# 2LD-20-mk-1_1_1.net
KiCad netlist of a schematic drawn in EAGLE
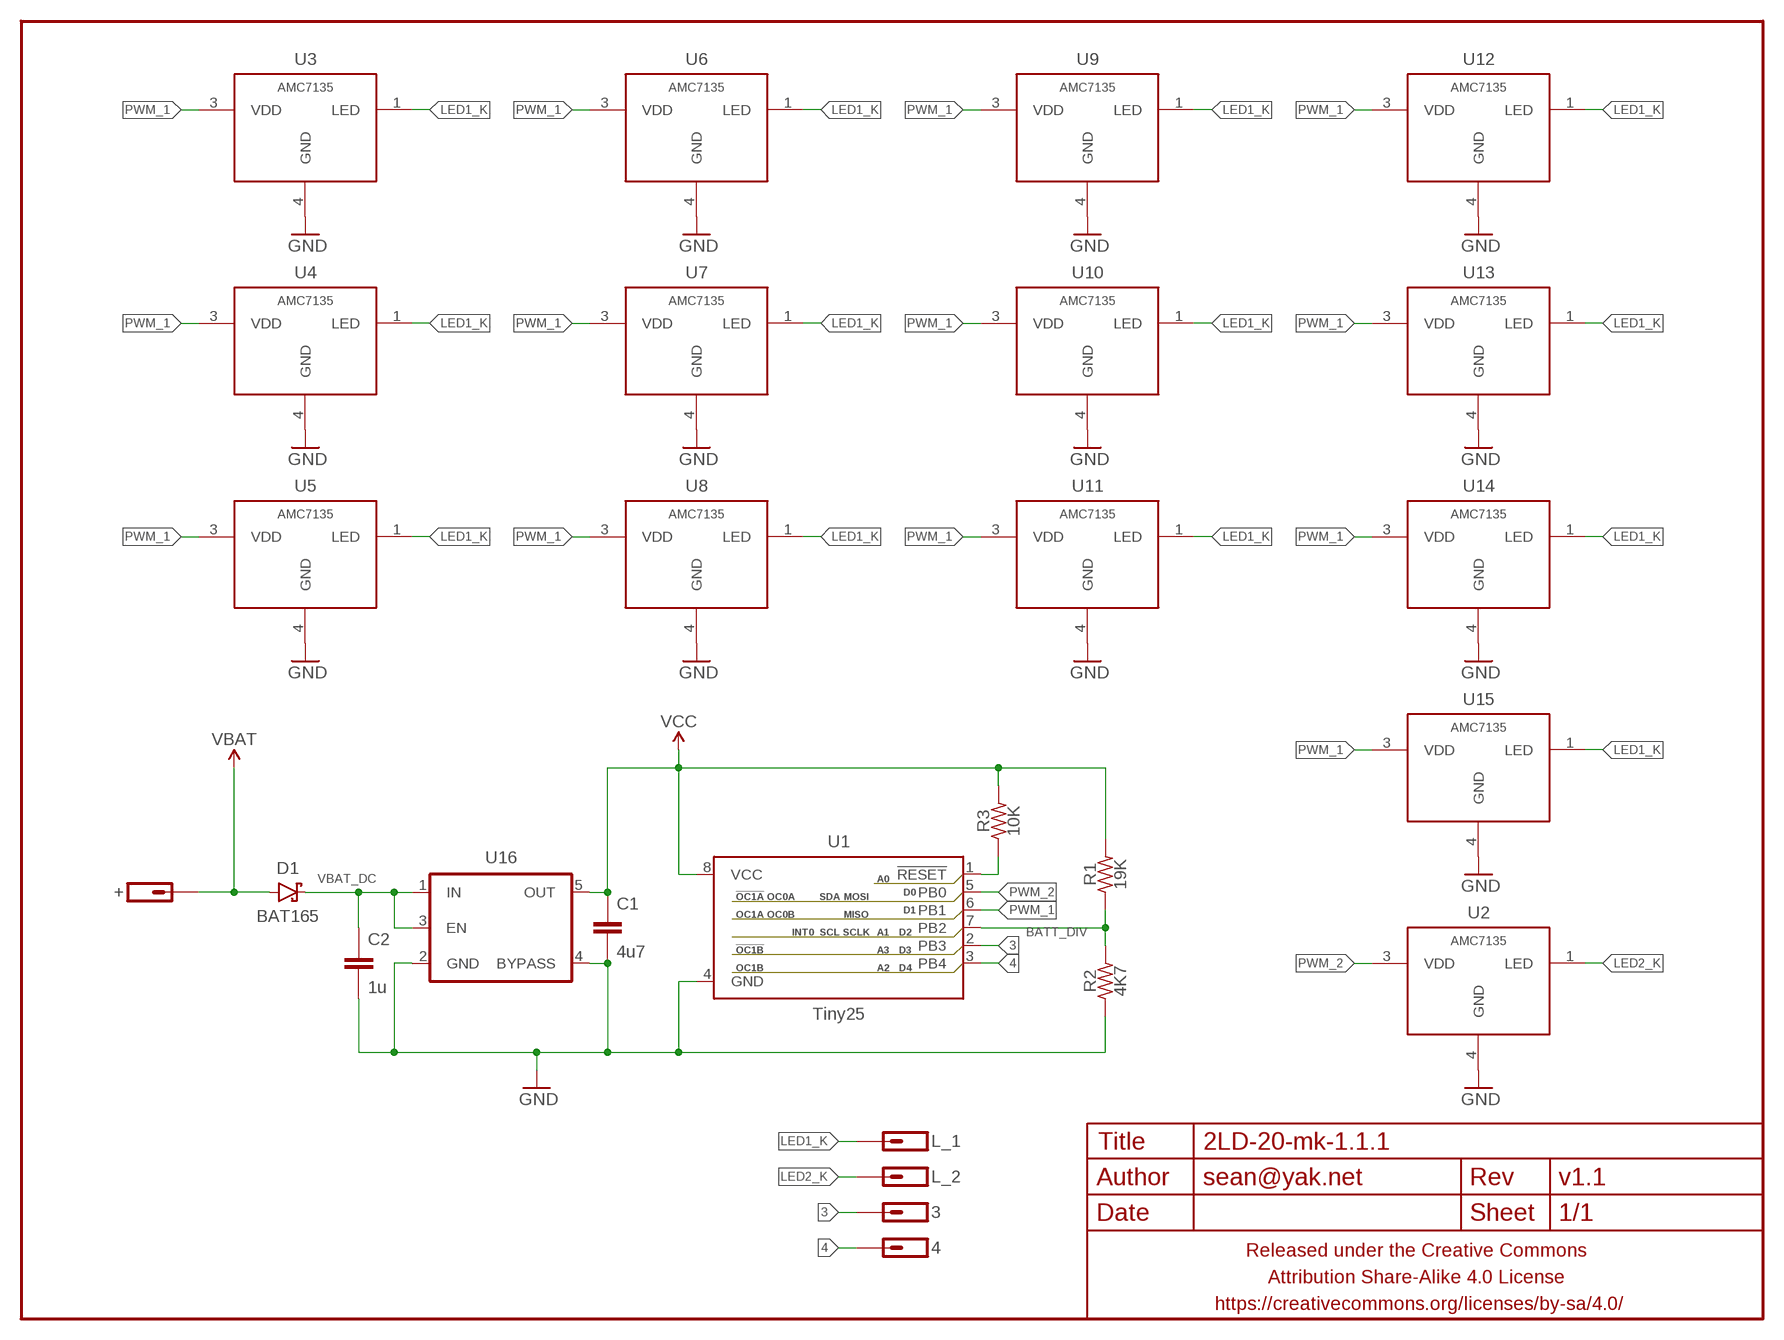
[diagram p0: schematic, sheet 1]

(export (version "E")
  (design (tool "Eeschema 10.0.6"))
  (components
    (comp (ref "+")
      (value "M01PTH-1MM-CIR-NS")
      (footprint "eagle-import:1X01-1MM-CIR-NS")
      (libsource (lib "eagle-import") (part "M01PTH-1MM-CIR-NS"))
    )
    (comp (ref "3")
      (value "M01SMD-0.8MM-DIA-NS")
      (footprint "eagle-import:1X01-SMD-0.8MM-DIA-NS")
      (libsource (lib "eagle-import") (part "M01SMD-0.8MM-DIA-NS"))
    )
    (comp (ref "4")
      (value "M01SMD-0.8MM-DIA-NS")
      (footprint "eagle-import:1X01-SMD-0.8MM-DIA-NS")
      (libsource (lib "eagle-import") (part "M01SMD-0.8MM-DIA-NS"))
    )
    (comp (ref "C1")
      (value "4u7")
      (footprint "eagle-import:C0603-TIGHTER")
      (libsource (lib "eagle-import") (part "CAPACITOR-CERAMICC0603-TIGHTER"))
    )
    (comp (ref "C2")
      (value "1u")
      (footprint "eagle-import:C0402")
      (libsource (lib "eagle-import") (part "CAPACITOR-CERAMICC0402"))
    )
    (comp (ref "D1")
      (value "BAT165")
      (footprint "eagle-import:SOD323-SCHOTTKY")
      (libsource (lib "eagle-import") (part "DIODE-SCHOTTKYSOD323"))
    )
    (comp (ref "FRAME1")
      (value "FRAME-LETTERNO_PACKAGE")
      (footprint "eagle-import:DUMMY")
      (fields (field (name "DESIGNER") "sean@yak.net") (field (name "VERSION") "v1.1"))
      (libsource (lib "eagle-import") (part "FRAME-LETTERNO_PACKAGE"))
    )
    (comp (ref "L_1")
      (value "M011X01-0.9MM-CIR")
      (footprint "eagle-import:1X01-0.9MM-CIR")
      (libsource (lib "eagle-import") (part "M011X01-0.9MM-CIR"))
    )
    (comp (ref "L_2")
      (value "M01PTH-0.8MM-CIR")
      (footprint "eagle-import:1X01-0.8MM-CIR")
      (libsource (lib "eagle-import") (part "M01PTH-0.8MM-CIR"))
    )
    (comp (ref "R1")
      (value "19K")
      (footprint "eagle-import:R0402")
      (libsource (lib "eagle-import") (part "RESISTORR0402"))
    )
    (comp (ref "R2")
      (value "4K7")
      (footprint "eagle-import:R0402")
      (libsource (lib "eagle-import") (part "RESISTORR0402"))
    )
    (comp (ref "R3")
      (value "10K")
      (footprint "eagle-import:R0402")
      (libsource (lib "eagle-import") (part "RESISTORR0402"))
    )
    (comp (ref "U1")
      (value "Tiny25")
      (footprint "eagle-import:SO08-NARROWER")
      (libsource (lib "eagle-import") (part "ATTINY13SOIC-NARROWPADS"))
    )
    (comp (ref "U2")
      (value "AMC7135")
      (footprint "eagle-import:SOT89-NOTHERM-ROUNDED-LESS")
      (libsource (lib "eagle-import") (part "AMC7135SOT-89-NOTHERM-ROUNDED-LESS"))
    )
    (comp (ref "U3")
      (value "AMC7135")
      (footprint "eagle-import:SOT89-NOTHERM-ROUNDED-LESS")
      (libsource (lib "eagle-import") (part "AMC7135SOT-89-NOTHERM-ROUNDED-LESS"))
    )
    (comp (ref "U4")
      (value "AMC7135")
      (footprint "eagle-import:SOT89-NOTHERM-ROUNDED-LESS")
      (libsource (lib "eagle-import") (part "AMC7135SOT-89-NOTHERM-ROUNDED-LESS"))
    )
    (comp (ref "U5")
      (value "AMC7135")
      (footprint "eagle-import:SOT89-NOTHERM-ROUNDED-LESS")
      (libsource (lib "eagle-import") (part "AMC7135SOT-89-NOTHERM-ROUNDED-LESS"))
    )
    (comp (ref "U6")
      (value "AMC7135")
      (footprint "eagle-import:SOT89-NOTHERM-ROUNDED-LESS")
      (libsource (lib "eagle-import") (part "AMC7135SOT-89-NOTHERM-ROUNDED-LESS"))
    )
    (comp (ref "U7")
      (value "AMC7135")
      (footprint "eagle-import:SOT89-NOTHERM-ROUNDED-LESS")
      (libsource (lib "eagle-import") (part "AMC7135SOT-89-NOTHERM-ROUNDED-LESS"))
    )
    (comp (ref "U8")
      (value "AMC7135")
      (footprint "eagle-import:SOT89-NOTHERM-ROUNDED-LESS")
      (libsource (lib "eagle-import") (part "AMC7135SOT-89-NOTHERM-ROUNDED-LESS"))
    )
    (comp (ref "U9")
      (value "AMC7135")
      (footprint "eagle-import:SOT89-NOTHERM-ROUNDED-LESS")
      (libsource (lib "eagle-import") (part "AMC7135SOT-89-NOTHERM-ROUNDED-LESS"))
    )
    (comp (ref "U10")
      (value "AMC7135")
      (footprint "eagle-import:SOT89-NOTHERM-ROUNDED-LESS")
      (libsource (lib "eagle-import") (part "AMC7135SOT-89-NOTHERM-ROUNDED-LESS"))
    )
    (comp (ref "U11")
      (value "AMC7135")
      (footprint "eagle-import:SOT89-NOTHERM-ROUNDED-LESS")
      (libsource (lib "eagle-import") (part "AMC7135SOT-89-NOTHERM-ROUNDED-LESS"))
    )
    (comp (ref "U12")
      (value "AMC7135")
      (footprint "eagle-import:SOT89-NOTHERM-ROUNDED-LESS")
      (libsource (lib "eagle-import") (part "AMC7135SOT-89-NOTHERM-ROUNDED-LESS"))
    )
    (comp (ref "U13")
      (value "AMC7135")
      (footprint "eagle-import:SOT89-NOTHERM-ROUNDED-LESS")
      (libsource (lib "eagle-import") (part "AMC7135SOT-89-NOTHERM-ROUNDED-LESS"))
    )
    (comp (ref "U14")
      (value "AMC7135")
      (footprint "eagle-import:SOT89-NOTHERM-ROUNDED-LESS")
      (libsource (lib "eagle-import") (part "AMC7135SOT-89-NOTHERM-ROUNDED-LESS"))
    )
    (comp (ref "U15")
      (value "AMC7135")
      (footprint "eagle-import:SOT89-NOTHERM-ROUNDED-LESS")
      (libsource (lib "eagle-import") (part "AMC7135SOT-89-NOTHERM-ROUNDED-LESS"))
    )
    (comp (ref "U16")
      (value "V_REG_SOT-23-5AP2112")
      (footprint "eagle-import:SOT23-5")
      (libsource (lib "eagle-import") (part "V_REG_SOT-23-5AP2112"))
    )
  )
  (nets
    (net (code "1") (name "/BATT_DIV") (class "Default")
      (node (ref "R1") (pin "1") (pinfunction "1_1") (pintype "passive"))
      (node (ref "R2") (pin "2") (pinfunction "2_2") (pintype "passive"))
      (node (ref "U1") (pin "7") (pinfunction "PB2_7") (pintype "bidirectional"))
    )
    (net (code "2") (name "/VBAT_DC") (class "Default")
      (node (ref "C2") (pin "1") (pinfunction "1_1") (pintype "passive"))
      (node (ref "D1") (pin "C") (pinfunction "C_C") (pintype "passive"))
      (node (ref "U16") (pin "1") (pinfunction "IN_1") (pintype "input"))
      (node (ref "U16") (pin "3") (pinfunction "EN_3") (pintype "input"))
    )
    (net (code "3") (name "3") (class "Default")
      (node (ref "3") (pin "P$1") (pinfunction "1_P$1") (pintype "passive"))
      (node (ref "U1") (pin "2") (pinfunction "PB3_2") (pintype "bidirectional"))
    )
    (net (code "4") (name "4") (class "Default")
      (node (ref "4") (pin "P$1") (pinfunction "1_P$1") (pintype "passive"))
      (node (ref "U1") (pin "3") (pinfunction "PB4_3") (pintype "bidirectional"))
    )
    (net (code "5") (name "GND") (class "Default")
      (node (ref "C1") (pin "2") (pinfunction "2_2") (pintype "passive"))
      (node (ref "C2") (pin "2") (pinfunction "2_2") (pintype "passive"))
      (node (ref "R2") (pin "1") (pinfunction "1_1") (pintype "passive"))
      (node (ref "U1") (pin "4") (pinfunction "GND_4") (pintype "bidirectional"))
      (node (ref "U10") (pin "4") (pinfunction "GND_4") (pintype "bidirectional"))
      (node (ref "U11") (pin "4") (pinfunction "GND_4") (pintype "bidirectional"))
      (node (ref "U12") (pin "4") (pinfunction "GND_4") (pintype "bidirectional"))
      (node (ref "U13") (pin "4") (pinfunction "GND_4") (pintype "bidirectional"))
      (node (ref "U14") (pin "4") (pinfunction "GND_4") (pintype "bidirectional"))
      (node (ref "U15") (pin "4") (pinfunction "GND_4") (pintype "bidirectional"))
      (node (ref "U16") (pin "2") (pinfunction "GND_2") (pintype "input"))
      (node (ref "U16") (pin "4") (pinfunction "BYPASS_4") (pintype "input"))
      (node (ref "U2") (pin "4") (pinfunction "GND_4") (pintype "bidirectional"))
      (node (ref "U3") (pin "4") (pinfunction "GND_4") (pintype "bidirectional"))
      (node (ref "U4") (pin "4") (pinfunction "GND_4") (pintype "bidirectional"))
      (node (ref "U5") (pin "4") (pinfunction "GND_4") (pintype "bidirectional"))
      (node (ref "U6") (pin "4") (pinfunction "GND_4") (pintype "bidirectional"))
      (node (ref "U7") (pin "4") (pinfunction "GND_4") (pintype "bidirectional"))
      (node (ref "U8") (pin "4") (pinfunction "GND_4") (pintype "bidirectional"))
      (node (ref "U9") (pin "4") (pinfunction "GND_4") (pintype "bidirectional"))
    )
    (net (code "6") (name "LED1_K") (class "Default")
      (node (ref "L_1") (pin "P$1") (pinfunction "1_P$1") (pintype "passive"))
      (node (ref "U10") (pin "1") (pinfunction "LED_1") (pintype "bidirectional"))
      (node (ref "U11") (pin "1") (pinfunction "LED_1") (pintype "bidirectional"))
      (node (ref "U12") (pin "1") (pinfunction "LED_1") (pintype "bidirectional"))
      (node (ref "U13") (pin "1") (pinfunction "LED_1") (pintype "bidirectional"))
      (node (ref "U14") (pin "1") (pinfunction "LED_1") (pintype "bidirectional"))
      (node (ref "U15") (pin "1") (pinfunction "LED_1") (pintype "bidirectional"))
      (node (ref "U3") (pin "1") (pinfunction "LED_1") (pintype "bidirectional"))
      (node (ref "U4") (pin "1") (pinfunction "LED_1") (pintype "bidirectional"))
      (node (ref "U5") (pin "1") (pinfunction "LED_1") (pintype "bidirectional"))
      (node (ref "U6") (pin "1") (pinfunction "LED_1") (pintype "bidirectional"))
      (node (ref "U7") (pin "1") (pinfunction "LED_1") (pintype "bidirectional"))
      (node (ref "U8") (pin "1") (pinfunction "LED_1") (pintype "bidirectional"))
      (node (ref "U9") (pin "1") (pinfunction "LED_1") (pintype "bidirectional"))
    )
    (net (code "7") (name "LED2_K") (class "Default")
      (node (ref "L_2") (pin "1") (pinfunction "1_1") (pintype "passive"))
      (node (ref "U2") (pin "1") (pinfunction "LED_1") (pintype "bidirectional"))
    )
    (net (code "8") (name "Net-(U1-~{RESET})") (class "Default")
      (node (ref "R3") (pin "1") (pinfunction "1_1") (pintype "passive"))
      (node (ref "U1") (pin "1") (pinfunction "~{RESET}_1") (pintype "bidirectional"))
    )
    (net (code "9") (name "PWM_1") (class "Default")
      (node (ref "U1") (pin "6") (pinfunction "PB1_6") (pintype "bidirectional"))
      (node (ref "U10") (pin "3") (pinfunction "VDD_3") (pintype "bidirectional"))
      (node (ref "U11") (pin "3") (pinfunction "VDD_3") (pintype "bidirectional"))
      (node (ref "U12") (pin "3") (pinfunction "VDD_3") (pintype "bidirectional"))
      (node (ref "U13") (pin "3") (pinfunction "VDD_3") (pintype "bidirectional"))
      (node (ref "U14") (pin "3") (pinfunction "VDD_3") (pintype "bidirectional"))
      (node (ref "U15") (pin "3") (pinfunction "VDD_3") (pintype "bidirectional"))
      (node (ref "U3") (pin "3") (pinfunction "VDD_3") (pintype "bidirectional"))
      (node (ref "U4") (pin "3") (pinfunction "VDD_3") (pintype "bidirectional"))
      (node (ref "U5") (pin "3") (pinfunction "VDD_3") (pintype "bidirectional"))
      (node (ref "U6") (pin "3") (pinfunction "VDD_3") (pintype "bidirectional"))
      (node (ref "U7") (pin "3") (pinfunction "VDD_3") (pintype "bidirectional"))
      (node (ref "U8") (pin "3") (pinfunction "VDD_3") (pintype "bidirectional"))
      (node (ref "U9") (pin "3") (pinfunction "VDD_3") (pintype "bidirectional"))
    )
    (net (code "10") (name "PWM_2") (class "Default")
      (node (ref "U1") (pin "5") (pinfunction "PB0_5") (pintype "bidirectional"))
      (node (ref "U2") (pin "3") (pinfunction "VDD_3") (pintype "bidirectional"))
    )
    (net (code "11") (name "VBAT") (class "Default")
      (node (ref "+") (pin "1") (pinfunction "1_1") (pintype "passive"))
      (node (ref "D1") (pin "A") (pinfunction "A_A") (pintype "passive"))
    )
    (net (code "12") (name "VCC") (class "Default")
      (node (ref "C1") (pin "1") (pinfunction "1_1") (pintype "passive"))
      (node (ref "R1") (pin "2") (pinfunction "2_2") (pintype "passive"))
      (node (ref "R3") (pin "2") (pinfunction "2_2") (pintype "passive"))
      (node (ref "U1") (pin "8") (pinfunction "VCC_8") (pintype "bidirectional"))
      (node (ref "U16") (pin "5") (pinfunction "OUT_5") (pintype "passive"))
    )
  )
)
